# EYEO_Flower3.net
KiCad netlist of a schematic drawn in EAGLE
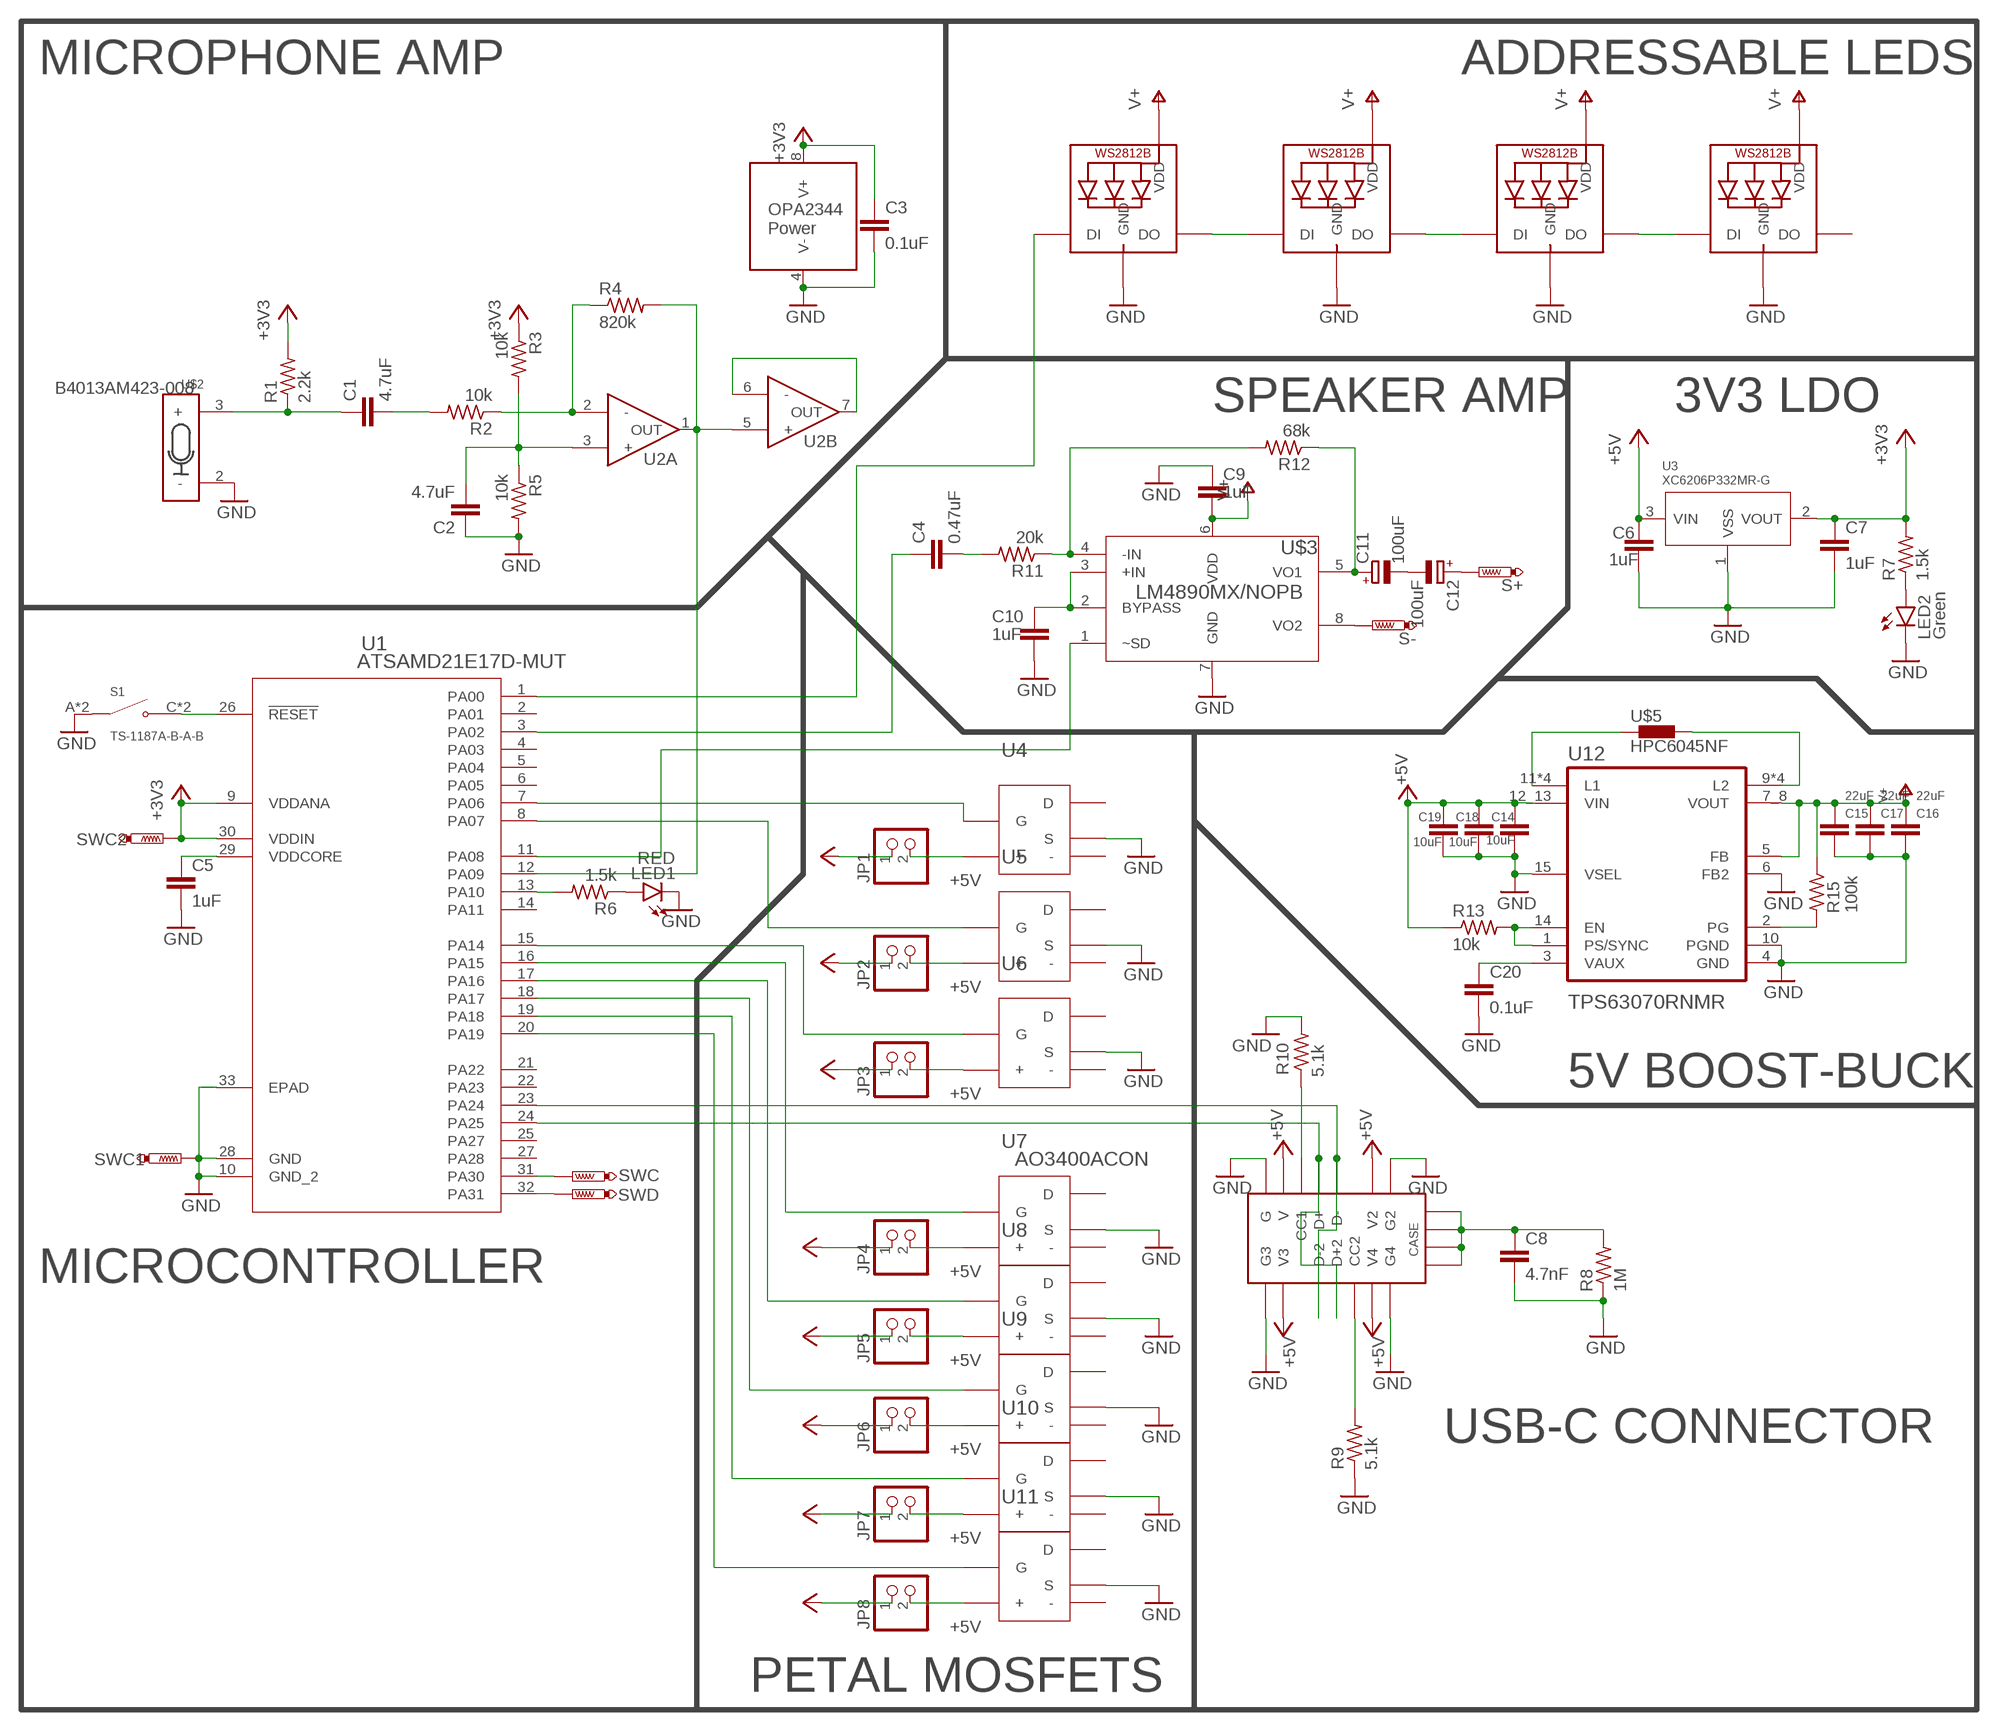
[diagram p0: schematic, sheet 1]

(export (version "E")
  (design (tool "Eeschema 10.0.6"))
  (components
    (comp (ref "C1")
      (value "4.7uF")
      (footprint "eagle-import:C0603")
      (fields (field (name "LCSC_PART") "C19666"))
      (libsource (lib "eagle-import") (part "C-EUC0603"))
    )
    (comp (ref "C2")
      (value "4.7uF")
      (footprint "eagle-import:C0603")
      (fields (field (name "LCSC_PART") "C19666"))
      (libsource (lib "eagle-import") (part "C-EUC0603"))
    )
    (comp (ref "C3")
      (value "0.1uF")
      (footprint "eagle-import:C0402")
      (fields (field (name "LCSC_PART") "C307331"))
      (libsource (lib "eagle-import") (part "C-EUC0402"))
    )
    (comp (ref "C4")
      (value "0.47uF")
      (footprint "eagle-import:C0603")
      (fields (field (name "LCSC_PART") "C1623"))
      (libsource (lib "eagle-import") (part "C-EUC0603"))
    )
    (comp (ref "C5")
      (value "1uF")
      (footprint "eagle-import:C0603")
      (fields (field (name "LCSC_PART") "C15849"))
      (libsource (lib "eagle-import") (part "C-EUC0603"))
    )
    (comp (ref "C6")
      (value "1uF")
      (footprint "eagle-import:C0603")
      (fields (field (name "LCSC_PART") "C15849"))
      (libsource (lib "eagle-import") (part "C-EUC0603"))
    )
    (comp (ref "C7")
      (value "1uF")
      (footprint "eagle-import:C0603")
      (fields (field (name "LCSC_PART") "C15849"))
      (libsource (lib "eagle-import") (part "C-EUC0603"))
    )
    (comp (ref "C8")
      (value "4.7nF")
      (footprint "eagle-import:C0402")
      (fields (field (name "LCSC_PART") "C1538"))
      (libsource (lib "eagle-import") (part "C-EUC0402"))
    )
    (comp (ref "C9")
      (value "1uF")
      (footprint "eagle-import:C0603")
      (fields (field (name "LCSC_PART") "C15849"))
      (libsource (lib "eagle-import") (part "C-EUC0603"))
    )
    (comp (ref "C10")
      (value "1uF")
      (footprint "eagle-import:C0603")
      (fields (field (name "LCSC_PART") "C15849"))
      (libsource (lib "eagle-import") (part "C-EUC0603"))
    )
    (comp (ref "C11")
      (value "100uF")
      (footprint "eagle-import:153CLV-0505")
      (fields (field (name "LCSC_PART") "C3347"))
      (libsource (lib "eagle-import") (part "CPOL-EU153CLV-0505"))
    )
    (comp (ref "C12")
      (value "100uF")
      (footprint "eagle-import:153CLV-0505")
      (fields (field (name "LCSC_PART") "C3347"))
      (libsource (lib "eagle-import") (part "CPOL-EU153CLV-0505"))
    )
    (comp (ref "C14")
      (value "10uF")
      (footprint "eagle-import:C0603")
      (fields (field (name "LCSC_PART") "C96446"))
      (libsource (lib "eagle-import") (part "C-EUC0603"))
    )
    (comp (ref "C15")
      (value "22uF")
      (footprint "eagle-import:C0603")
      (fields (field (name "LCSC_PART") "C59461"))
      (libsource (lib "eagle-import") (part "C-EUC0603"))
    )
    (comp (ref "C16")
      (value "22uF")
      (footprint "eagle-import:C0603")
      (fields (field (name "LCSC_PART") "C59461"))
      (libsource (lib "eagle-import") (part "C-EUC0603"))
    )
    (comp (ref "C17")
      (value "22uF")
      (footprint "eagle-import:C0603")
      (fields (field (name "LCSC_PART") "C59461"))
      (libsource (lib "eagle-import") (part "C-EUC0603"))
    )
    (comp (ref "C18")
      (value "10uF")
      (footprint "eagle-import:C0603")
      (fields (field (name "LCSC_PART") "C96446"))
      (libsource (lib "eagle-import") (part "C-EUC0603"))
    )
    (comp (ref "C19")
      (value "10uF")
      (footprint "eagle-import:C0603")
      (fields (field (name "LCSC_PART") "C96446"))
      (libsource (lib "eagle-import") (part "C-EUC0603"))
    )
    (comp (ref "C20")
      (value "0.1uF")
      (footprint "eagle-import:C0402")
      (fields (field (name "LCSC_PART") "C307331"))
      (libsource (lib "eagle-import") (part "C-EUC0402"))
    )
    (comp (ref "JP1")
      (value "PINHD-1X2")
      (footprint "eagle-import:1X02")
      (fields (field (name "LCSC_PART") "C2889984"))
      (libsource (lib "eagle-import") (part "PINHD-1X2"))
    )
    (comp (ref "JP2")
      (value "PINHD-1X2")
      (footprint "eagle-import:1X02")
      (fields (field (name "LCSC_PART") "C2889984"))
      (libsource (lib "eagle-import") (part "PINHD-1X2"))
    )
    (comp (ref "JP3")
      (value "PINHD-1X2")
      (footprint "eagle-import:1X02")
      (fields (field (name "LCSC_PART") "C2889984"))
      (libsource (lib "eagle-import") (part "PINHD-1X2"))
    )
    (comp (ref "JP4")
      (value "PINHD-1X2")
      (footprint "eagle-import:1X02")
      (fields (field (name "LCSC_PART") "C2889984"))
      (libsource (lib "eagle-import") (part "PINHD-1X2"))
    )
    (comp (ref "JP5")
      (value "PINHD-1X2")
      (footprint "eagle-import:1X02")
      (fields (field (name "LCSC_PART") "C2889984"))
      (libsource (lib "eagle-import") (part "PINHD-1X2"))
    )
    (comp (ref "JP6")
      (value "PINHD-1X2")
      (footprint "eagle-import:1X02")
      (fields (field (name "LCSC_PART") "C2889984"))
      (libsource (lib "eagle-import") (part "PINHD-1X2"))
    )
    (comp (ref "JP7")
      (value "PINHD-1X2")
      (footprint "eagle-import:1X02")
      (fields (field (name "LCSC_PART") "C2889984"))
      (libsource (lib "eagle-import") (part "PINHD-1X2"))
    )
    (comp (ref "JP8")
      (value "PINHD-1X2")
      (footprint "eagle-import:1X02")
      (fields (field (name "LCSC_PART") "C2889984"))
      (libsource (lib "eagle-import") (part "PINHD-1X2"))
    )
    (comp (ref "LED1")
      (value "RED")
      (footprint "eagle-import:CHIPLED_0805")
      (fields (field (name "LCSC_PART") "C84256"))
      (libsource (lib "eagle-import") (part "LEDCHIPLED_0805"))
    )
    (comp (ref "LED2")
      (value "Green")
      (footprint "eagle-import:CHIPLED_0603")
      (fields (field (name "LCSC_PART") "C72043"))
      (libsource (lib "eagle-import") (part "LEDCHIPLED_0603"))
    )
    (comp (ref "LED3")
      (value "WS2812B5050")
      (footprint "eagle-import:WS2812B")
      (fields
        (field (name "LCSC_PART") "C2761795")
        (field (name "MF") "Worldsemi")
        (field (name "MP") "WS2812B")
      )
      (libsource (lib "eagle-import") (part "WS2812B5050"))
    )
    (comp (ref "LED4")
      (value "WS2812B5050")
      (footprint "eagle-import:WS2812B")
      (fields
        (field (name "LCSC_PART") "C2761795")
        (field (name "MF") "Worldsemi")
        (field (name "MP") "WS2812B")
      )
      (libsource (lib "eagle-import") (part "WS2812B5050"))
    )
    (comp (ref "LED5")
      (value "WS2812B5050")
      (footprint "eagle-import:WS2812B")
      (fields
        (field (name "LCSC_PART") "C2761795")
        (field (name "MF") "Worldsemi")
        (field (name "MP") "WS2812B")
      )
      (libsource (lib "eagle-import") (part "WS2812B5050"))
    )
    (comp (ref "LED6")
      (value "WS2812B5050")
      (footprint "eagle-import:WS2812B")
      (fields
        (field (name "LCSC_PART") "C2761795")
        (field (name "MF") "Worldsemi")
        (field (name "MP") "WS2812B")
      )
      (libsource (lib "eagle-import") (part "WS2812B5050"))
    )
    (comp (ref "R1")
      (value "2.2k")
      (footprint "eagle-import:R0402")
      (fields (field (name "LCSC_PART") "C25879"))
      (libsource (lib "eagle-import") (part "R-US_R0402"))
    )
    (comp (ref "R2")
      (value "10k")
      (footprint "eagle-import:R0402")
      (fields (field (name "LCSC_PART") "C25744"))
      (libsource (lib "eagle-import") (part "R-US_R0402"))
    )
    (comp (ref "R3")
      (value "10k")
      (footprint "eagle-import:R0402")
      (fields (field (name "LCSC_PART") "C25744"))
      (libsource (lib "eagle-import") (part "R-US_R0402"))
    )
    (comp (ref "R4")
      (value "820k")
      (footprint "eagle-import:R0402")
      (fields (field (name "LCSC_PART") "C67558"))
      (libsource (lib "eagle-import") (part "R-US_R0402"))
    )
    (comp (ref "R5")
      (value "10k")
      (footprint "eagle-import:R0402")
      (fields (field (name "LCSC_PART") "C25744"))
      (libsource (lib "eagle-import") (part "R-US_R0402"))
    )
    (comp (ref "R6")
      (value "1.5k")
      (footprint "eagle-import:R0402")
      (fields (field (name "LCSC_PART") "C25867"))
      (libsource (lib "eagle-import") (part "R-US_R0402"))
    )
    (comp (ref "R7")
      (value "1.5k")
      (footprint "eagle-import:R0402")
      (fields (field (name "LCSC_PART") "C25867"))
      (libsource (lib "eagle-import") (part "R-US_R0402"))
    )
    (comp (ref "R8")
      (value "1M")
      (footprint "eagle-import:R0402")
      (fields (field (name "LCSC_PART") "C26083"))
      (libsource (lib "eagle-import") (part "R-US_R0402"))
    )
    (comp (ref "R9")
      (value "5.1k")
      (footprint "eagle-import:R0402")
      (fields (field (name "LCSC_PART") "C25905"))
      (libsource (lib "eagle-import") (part "R-US_R0402"))
    )
    (comp (ref "R10")
      (value "5.1k")
      (footprint "eagle-import:R0402")
      (fields (field (name "LCSC_PART") "C25905"))
      (libsource (lib "eagle-import") (part "R-US_R0402"))
    )
    (comp (ref "R11")
      (value "20k")
      (footprint "eagle-import:R0402")
      (fields (field (name "LCSC_PART") "C25765"))
      (libsource (lib "eagle-import") (part "R-US_R0402"))
    )
    (comp (ref "R12")
      (value "68k")
      (footprint "eagle-import:R0402")
      (fields (field (name "LCSC_PART") "C36871"))
      (libsource (lib "eagle-import") (part "R-US_R0402"))
    )
    (comp (ref "R13")
      (value "10k")
      (footprint "eagle-import:R0402")
      (fields (field (name "LCSC_PART") "C25744"))
      (libsource (lib "eagle-import") (part "R-US_R0402"))
    )
    (comp (ref "R15")
      (value "100k")
      (footprint "eagle-import:R0402")
      (fields (field (name "LCSC_PART") "C25741"))
      (libsource (lib "eagle-import") (part "R-US_R0402"))
    )
    (comp (ref "S+")
      (value "PTR11MM")
      (footprint "eagle-import:1MM")
      (fields (field (name "LCSC_PART") "C238122"))
      (libsource (lib "eagle-import") (part "PTR11MM"))
    )
    (comp (ref "S-")
      (value "PTR11MM")
      (footprint "eagle-import:1MM")
      (fields (field (name "LCSC_PART") "C238122"))
      (libsource (lib "eagle-import") (part "PTR11MM"))
    )
    (comp (ref "S1")
      (value "TS-1187A-B-A-B")
      (footprint "eagle-import:SW_TS-1187A-B-A-B")
      (fields (field (name "MF") "XKB Industrial Precision") (field (name "LCSC_PART") "C318884"))
      (libsource (lib "eagle-import") (part "TS-1187A-B-A-B"))
    )
    (comp (ref "SWC")
      (value "PTR1PAD1-13")
      (footprint "eagle-import:P1-13")
      (libsource (lib "eagle-import") (part "PTR1PAD1-13"))
    )
    (comp (ref "SWC1")
      (value "PTR1PAD1-13")
      (footprint "eagle-import:P1-13")
      (libsource (lib "eagle-import") (part "PTR1PAD1-13"))
    )
    (comp (ref "SWC2")
      (value "PTR1PAD1-13")
      (footprint "eagle-import:P1-13")
      (libsource (lib "eagle-import") (part "PTR1PAD1-13"))
    )
    (comp (ref "SWD")
      (value "PTR1PAD1-13")
      (footprint "eagle-import:P1-13")
      (libsource (lib "eagle-import") (part "PTR1PAD1-13"))
    )
    (comp (ref "U$1")
      (value "USB-C")
      (footprint "eagle-import:918-418K2022Y40000")
      (fields (field (name "LCSC_PART") "C168704"))
      (libsource (lib "eagle-import") (part "USB-C"))
    )
    (comp (ref "U$2")
      (value "B4013AM423")
      (footprint "eagle-import:B4013AM423")
      (fields (field (name "LCSC_PART") "C233794") (field (name "NUM") "B4013AM423-008 "))
      (libsource (lib "eagle-import") (part "B4013AM423"))
    )
    (comp (ref "U$3")
      (value "LM4890MX/NOPB")
      (footprint "eagle-import:M08A")
      (fields
        (field (name "LCSC_PART") "C117476")
        (field (name "COPYRIGHT") "Copyright (C) 2022 Ultra Librarian. All rights reserved.")
      )
      (libsource (lib "eagle-import") (part "LM4890MX/NOPB"))
    )
    (comp (ref "U$5")
      (value "HPC6045NF")
      (footprint "eagle-import:HPC6045NF")
      (fields (field (name "LCSC_PART") "C357076"))
      (libsource (lib "eagle-import") (part "HPC6045NF"))
    )
    (comp (ref "U1")
      (value "ATSAMD21E17D-MUT")
      (footprint "eagle-import:QFN32_5X5MC_MCH")
      (fields (field (name "COPYRIGHT") "Copyright (C) 2022 Ultra Librarian. All rights reserved."))
      (libsource (lib "eagle-import") (part "ATSAMD21E17D-MUT"))
    )
    (comp (ref "U2")
      (value "OPA2344UA")
      (footprint "eagle-import:D8")
      (fields
        (field (name "LCSC_PART") "C202213")
        (field (name "COPYRIGHT") "Copyright (C) 2022 Ultra Librarian. All rights reserved.")
      )
      (libsource (lib "eagle-import") (part "OPA2344UA"))
    )
    (comp (ref "U3")
      (value "XC6206P332MR-G")
      (footprint "eagle-import:SOT-23")
      (fields (field (name "MF") "Torex") (field (name "LCSC_PART") "C5446"))
      (libsource (lib "eagle-import") (part "PMIC-LDO-XC6206P332MR-G(SOT23)"))
    )
    (comp (ref "U4")
      (value "AO3400ACON")
      (footprint "eagle-import:SOT23-BCE-CON")
      (fields (field (name "LCSC_PART") "C20917"))
      (libsource (lib "eagle-import") (part "AO3400ACON"))
    )
    (comp (ref "U5")
      (value "AO3400ACON")
      (footprint "eagle-import:SOT23-BCE-CON")
      (fields (field (name "LCSC_PART") "C20917"))
      (libsource (lib "eagle-import") (part "AO3400ACON"))
    )
    (comp (ref "U6")
      (value "AO3400ACON")
      (footprint "eagle-import:SOT23-BCE-CON")
      (fields (field (name "LCSC_PART") "C20917"))
      (libsource (lib "eagle-import") (part "AO3400ACON"))
    )
    (comp (ref "U7")
      (value "AO3400ACON")
      (footprint "eagle-import:SOT23-BCE-CON")
      (fields (field (name "LCSC_PART") "C20917"))
      (libsource (lib "eagle-import") (part "AO3400ACON"))
    )
    (comp (ref "U8")
      (value "AO3400ACON")
      (footprint "eagle-import:SOT23-BCE-CON")
      (fields (field (name "LCSC_PART") "C20917"))
      (libsource (lib "eagle-import") (part "AO3400ACON"))
    )
    (comp (ref "U9")
      (value "AO3400ACON")
      (footprint "eagle-import:SOT23-BCE-CON")
      (fields (field (name "LCSC_PART") "C20917"))
      (libsource (lib "eagle-import") (part "AO3400ACON"))
    )
    (comp (ref "U10")
      (value "AO3400ACON")
      (footprint "eagle-import:SOT23-BCE-CON")
      (fields (field (name "LCSC_PART") "C20917"))
      (libsource (lib "eagle-import") (part "AO3400ACON"))
    )
    (comp (ref "U11")
      (value "AO3400ACON")
      (footprint "eagle-import:SOT23-BCE-CON")
      (fields (field (name "LCSC_PART") "C20917"))
      (libsource (lib "eagle-import") (part "AO3400ACON"))
    )
    (comp (ref "U12")
      (value "TPS63070RNMR")
      (footprint "eagle-import:VREG_TPS63070RNMR")
      (fields (field (name "LCSC_PART") "C2876599") (field (name "MF") "Texas Instruments"))
      (libsource (lib "eagle-import") (part "TPS63070RNMR"))
    )
  )
  (nets
    (net (code "1") (name "+3V3") (class "Default")
      (node (ref "C3") (pin "1") (pinfunction "1_1") (pintype "passive"))
      (node (ref "C7") (pin "1") (pinfunction "1_1") (pintype "passive"))
      (node (ref "R1") (pin "2") (pinfunction "2_2") (pintype "passive"))
      (node (ref "R3") (pin "1") (pinfunction "1_1") (pintype "passive"))
      (node (ref "R7") (pin "2") (pinfunction "2_2") (pintype "passive"))
      (node (ref "SWC2") (pin "TP") (pinfunction "TP_TP") (pintype "input"))
      (node (ref "U1") (pin "30") (pinfunction "VDDIN_30") (pintype "power_in"))
      (node (ref "U1") (pin "9") (pinfunction "VDDANA_9") (pintype "power_in"))
      (node (ref "U2") (pin "8") (pinfunction "V+_8") (pintype "bidirectional"))
      (node (ref "U3") (pin "2") (pinfunction "VOUT_2") (pintype "output"))
    )
    (net (code "2") (name "+5V") (class "Default")
      (node (ref "C14") (pin "1") (pinfunction "1_1") (pintype "passive"))
      (node (ref "C18") (pin "1") (pinfunction "1_1") (pintype "passive"))
      (node (ref "C19") (pin "1") (pinfunction "1_1") (pintype "passive"))
      (node (ref "C6") (pin "1") (pinfunction "1_1") (pintype "passive"))
      (node (ref "JP1") (pin "1") (pinfunction "1_1") (pintype "passive"))
      (node (ref "JP2") (pin "1") (pinfunction "1_1") (pintype "passive"))
      (node (ref "JP3") (pin "1") (pinfunction "1_1") (pintype "passive"))
      (node (ref "JP4") (pin "1") (pinfunction "1_1") (pintype "passive"))
      (node (ref "JP5") (pin "1") (pinfunction "1_1") (pintype "passive"))
      (node (ref "JP6") (pin "1") (pinfunction "1_1") (pintype "passive"))
      (node (ref "JP7") (pin "1") (pinfunction "1_1") (pintype "passive"))
      (node (ref "JP8") (pin "1") (pinfunction "1_1") (pintype "passive"))
      (node (ref "R13") (pin "1") (pinfunction "1_1") (pintype "passive"))
      (node (ref "U$1") (pin "V") (pinfunction "V_V") (pintype "bidirectional"))
      (node (ref "U$1") (pin "V2") (pinfunction "V2_V2") (pintype "bidirectional"))
      (node (ref "U$1") (pin "V3") (pinfunction "V3_V3") (pintype "bidirectional"))
      (node (ref "U$1") (pin "V4") (pinfunction "V4_V4") (pintype "bidirectional"))
      (node (ref "U12") (pin "12_13") (pinfunction "VIN_12_13") (pintype "input"))
      (node (ref "U3") (pin "3") (pinfunction "VIN_3") (pintype "input"))
    )
    (net (code "3") (name "GND") (class "Default")
      (node (ref "C10") (pin "2") (pinfunction "2_2") (pintype "passive"))
      (node (ref "C14") (pin "2") (pinfunction "2_2") (pintype "passive"))
      (node (ref "C15") (pin "2") (pinfunction "2_2") (pintype "passive"))
      (node (ref "C16") (pin "2") (pinfunction "2_2") (pintype "passive"))
      (node (ref "C17") (pin "2") (pinfunction "2_2") (pintype "passive"))
      (node (ref "C18") (pin "2") (pinfunction "2_2") (pintype "passive"))
      (node (ref "C19") (pin "2") (pinfunction "2_2") (pintype "passive"))
      (node (ref "C2") (pin "1") (pinfunction "1_1") (pintype "passive"))
      (node (ref "C20") (pin "2") (pinfunction "2_2") (pintype "passive"))
      (node (ref "C3") (pin "2") (pinfunction "2_2") (pintype "passive"))
      (node (ref "C5") (pin "2") (pinfunction "2_2") (pintype "passive"))
      (node (ref "C6") (pin "2") (pinfunction "2_2") (pintype "passive"))
      (node (ref "C7") (pin "2") (pinfunction "2_2") (pintype "passive"))
      (node (ref "C8") (pin "2") (pinfunction "2_2") (pintype "passive"))
      (node (ref "C9") (pin "1") (pinfunction "1_1") (pintype "passive"))
      (node (ref "LED1") (pin "C") (pinfunction "C_C") (pintype "passive"))
      (node (ref "LED2") (pin "C") (pinfunction "C_C") (pintype "passive"))
      (node (ref "LED3") (pin "3-GND") (pinfunction "GND_3-GND") (pintype "power_in"))
      (node (ref "LED4") (pin "3-GND") (pinfunction "GND_3-GND") (pintype "power_in"))
      (node (ref "LED5") (pin "3-GND") (pinfunction "GND_3-GND") (pintype "power_in"))
      (node (ref "LED6") (pin "3-GND") (pinfunction "GND_3-GND") (pintype "power_in"))
      (node (ref "R10") (pin "2") (pinfunction "2_2") (pintype "passive"))
      (node (ref "R5") (pin "2") (pinfunction "2_2") (pintype "passive"))
      (node (ref "R8") (pin "1") (pinfunction "1_1") (pintype "passive"))
      (node (ref "R9") (pin "1") (pinfunction "1_1") (pintype "passive"))
      (node (ref "S1") (pin "A") (pinfunction "COM_A") (pintype "passive"))
      (node (ref "S1") (pin "B") (pinfunction "COM_B") (pintype "passive"))
      (node (ref "SWC1") (pin "TP") (pinfunction "TP_TP") (pintype "input"))
      (node (ref "U$1") (pin "G") (pinfunction "G_G") (pintype "bidirectional"))
      (node (ref "U$1") (pin "G2") (pinfunction "G2_G2") (pintype "bidirectional"))
      (node (ref "U$1") (pin "G3") (pinfunction "G3_G3") (pintype "bidirectional"))
      (node (ref "U$1") (pin "G4") (pinfunction "G4_G4") (pintype "bidirectional"))
      (node (ref "U$2") (pin "2") (pinfunction "-_2") (pintype "bidirectional"))
      (node (ref "U$3") (pin "7") (pinfunction "GND_7") (pintype "power_in"))
      (node (ref "U1") (pin "10") (pinfunction "GND_2_10") (pintype "passive"))
      (node (ref "U1") (pin "28") (pinfunction "GND_28") (pintype "passive"))
      (node (ref "U1") (pin "33") (pinfunction "EPAD_33") (pintype "passive"))
      (node (ref "U10") (pin "S") (pinfunction "S_S") (pintype "passive"))
      (node (ref "U11") (pin "S") (pinfunction "S_S") (pintype "passive"))
      (node (ref "U12") (pin "10") (pinfunction "PGND_10") (pintype "power_in"))
      (node (ref "U12") (pin "15") (pinfunction "VSEL_15") (pintype "input"))
      (node (ref "U12") (pin "4") (pinfunction "GND_4") (pintype "power_in"))
      (node (ref "U12") (pin "6") (pinfunction "FB2_6") (pintype "output"))
      (node (ref "U2") (pin "4") (pinfunction "V-_4") (pintype "bidirectional"))
      (node (ref "U3") (pin "1") (pinfunction "VSS_1") (pintype "power_in"))
      (node (ref "U4") (pin "S") (pinfunction "S_S") (pintype "passive"))
      (node (ref "U5") (pin "S") (pinfunction "S_S") (pintype "passive"))
      (node (ref "U6") (pin "S") (pinfunction "S_S") (pintype "passive"))
      (node (ref "U7") (pin "S") (pinfunction "S_S") (pintype "passive"))
      (node (ref "U8") (pin "S") (pinfunction "S_S") (pintype "passive"))
      (node (ref "U9") (pin "S") (pinfunction "S_S") (pintype "passive"))
    )
    (net (code "4") (name "Net-(C1-Pad2)") (class "Default")
      (node (ref "C1") (pin "2") (pinfunction "2_2") (pintype "passive"))
      (node (ref "R2") (pin "2") (pinfunction "2_2") (pintype "passive"))
    )
    (net (code "5") (name "Net-(C4-Pad2)") (class "Default")
      (node (ref "C4") (pin "2") (pinfunction "2_2") (pintype "passive"))
      (node (ref "R11") (pin "2") (pinfunction "2_2") (pintype "passive"))
    )
    (net (code "6") (name "Net-(C11-Pad-)") (class "Default")
      (node (ref "C11") (pin "-") (pinfunction "-_-") (pintype "passive"))
      (node (ref "C12") (pin "-") (pinfunction "-_-") (pintype "passive"))
    )
    (net (code "7") (name "Net-(C12-Pad+)") (class "Default")
      (node (ref "C12") (pin "+") (pinfunction "+_+") (pintype "passive"))
      (node (ref "S+") (pin "TP") (pinfunction "TP_TP") (pintype "input"))
    )
    (net (code "8") (name "Net-(JP1-Pad2)") (class "Default")
      (node (ref "JP1") (pin "2") (pinfunction "2_2") (pintype "passive"))
      (node (ref "U4") (pin "+") (pinfunction "+_+") (pintype "bidirectional"))
    )
    (net (code "9") (name "Net-(JP2-Pad2)") (class "Default")
      (node (ref "JP2") (pin "2") (pinfunction "2_2") (pintype "passive"))
      (node (ref "U5") (pin "+") (pinfunction "+_+") (pintype "bidirectional"))
    )
    (net (code "10") (name "Net-(JP3-Pad2)") (class "Default")
      (node (ref "JP3") (pin "2") (pinfunction "2_2") (pintype "passive"))
      (node (ref "U6") (pin "+") (pinfunction "+_+") (pintype "bidirectional"))
    )
    (net (code "11") (name "Net-(JP4-Pad2)") (class "Default")
      (node (ref "JP4") (pin "2") (pinfunction "2_2") (pintype "passive"))
      (node (ref "U7") (pin "+") (pinfunction "+_+") (pintype "bidirectional"))
    )
    (net (code "12") (name "Net-(JP5-Pad2)") (class "Default")
      (node (ref "JP5") (pin "2") (pinfunction "2_2") (pintype "passive"))
      (node (ref "U8") (pin "+") (pinfunction "+_+") (pintype "bidirectional"))
    )
    (net (code "13") (name "Net-(JP6-Pad2)") (class "Default")
      (node (ref "JP6") (pin "2") (pinfunction "2_2") (pintype "passive"))
      (node (ref "U9") (pin "+") (pinfunction "+_+") (pintype "bidirectional"))
    )
    (net (code "14") (name "Net-(JP7-Pad2)") (class "Default")
      (node (ref "JP7") (pin "2") (pinfunction "2_2") (pintype "passive"))
      (node (ref "U10") (pin "+") (pinfunction "+_+") (pintype "bidirectional"))
    )
    (net (code "15") (name "Net-(JP8-Pad2)") (class "Default")
      (node (ref "JP8") (pin "2") (pinfunction "2_2") (pintype "passive"))
      (node (ref "U11") (pin "+") (pinfunction "+_+") (pintype "bidirectional"))
    )
    (net (code "16") (name "Net-(LED1-PadA)") (class "Default")
      (node (ref "LED1") (pin "A") (pinfunction "A_A") (pintype "passive"))
      (node (ref "R6") (pin "1") (pinfunction "1_1") (pintype "passive"))
    )
    (net (code "17") (name "Net-(LED2-PadA)") (class "Default")
      (node (ref "LED2") (pin "A") (pinfunction "A_A") (pintype "passive"))
      (node (ref "R7") (pin "1") (pinfunction "1_1") (pintype "passive"))
    )
    (net (code "18") (name "Net-(LED3-DI)") (class "Default")
      (node (ref "LED3") (pin "4-DIN") (pinfunction "DI_4-DIN") (pintype "input"))
      (node (ref "U1") (pin "1") (pinfunction "PA00_1") (pintype "bidirectional"))
    )
    (net (code "19") (name "Net-(LED3-DO)") (class "Default")
      (node (ref "LED3") (pin "2-DOUT") (pinfunction "DO_2-DOUT") (pintype "output"))
      (node (ref "LED4") (pin "4-DIN") (pinfunction "DI_4-DIN") (pintype "input"))
    )
    (net (code "20") (name "Net-(LED4-DO)") (class "Default")
      (node (ref "LED4") (pin "2-DOUT") (pinfunction "DO_2-DOUT") (pintype "output"))
      (node (ref "LED5") (pin "4-DIN") (pinfunction "DI_4-DIN") (pintype "input"))
    )
    (net (code "21") (name "Net-(LED5-DO)") (class "Default")
      (node (ref "LED5") (pin "2-DOUT") (pinfunction "DO_2-DOUT") (pintype "output"))
      (node (ref "LED6") (pin "4-DIN") (pinfunction "DI_4-DIN") (pintype "input"))
    )
    (net (code "22") (name "Net-(R9-Pad2)") (class "Default")
      (node (ref "R9") (pin "2") (pinfunction "2_2") (pintype "passive"))
      (node (ref "U$1") (pin "CC2") (pinfunction "CC2_CC2") (pintype "bidirectional"))
    )
    (net (code "23") (name "Net-(R10-Pad1)") (class "Default")
      (node (ref "R10") (pin "1") (pinfunction "1_1") (pintype "passive"))
      (node (ref "U$1") (pin "CC1") (pinfunction "CC1_CC1") (pintype "bidirectional"))
    )
    (net (code "24") (name "Net-(U$1-1)") (class "Default")
      (node (ref "C8") (pin "1") (pinfunction "1_1") (pintype "passive"))
      (node (ref "R8") (pin "2") (pinfunction "2_2") (pintype "passive"))
      (node (ref "U$1") (pin "OG1") (pinfunction "1_OG1") (pintype "bidirectional"))
      (node (ref "U$1") (pin "OG2") (pinfunction "2_OG2") (pintype "bidirectional"))
      (node (ref "U$1") (pin "OG3") (pinfunction "3_OG3") (pintype "bidirectional"))
      (node (ref "U$1") (pin "OG4") (pinfunction "4_OG4") (pintype "bidirectional"))
    )
    (net (code "25") (name "Net-(U$2-+)") (class "Default")
      (node (ref "C1") (pin "1") (pinfunction "1_1") (pintype "passive"))
      (node (ref "R1") (pin "1") (pinfunction "1_1") (pintype "passive"))
      (node (ref "U$2") (pin "3") (pinfunction "+_3") (pintype "bidirectional"))
    )
    (net (code "26") (name "Net-(U$3-+IN)") (class "Default")
      (node (ref "C10") (pin "1") (pinfunction "1_1") (pintype "passive"))
      (node (ref "U$3") (pin "2") (pinfunction "BYPASS_2") (pintype "passive"))
      (node (ref "U$3") (pin "3") (pinfunction "+IN_3") (pintype "input"))
    )
    (net (code "27") (name "Net-(U$3--IN)") (class "Default")
      (node (ref "R11") (pin "1") (pinfunction "1_1") (pintype "passive"))
      (node (ref "R12") (pin "2") (pinfunction "2_2") (pintype "passive"))
      (node (ref "U$3") (pin "4") (pinfunction "-IN_4") (pintype "input"))
    )
    (net (code "28") (name "Net-(U$3-VO1)") (class "Default")
      (node (ref "C11") (pin "+") (pinfunction "+_+") (pintype "passive"))
      (node (ref "R12") (pin "1") (pinfunction "1_1") (pintype "passive"))
      (node (ref "U$3") (pin "5") (pinfunction "VO1_5") (pintype "output"))
    )
    (net (code "29") (name "Net-(U$3-VO2)") (class "Default")
      (node (ref "S-") (pin "TP") (pinfunction "TP_TP") (pintype "input"))
      (node (ref "U$3") (pin "8") (pinfunction "VO2_8") (pintype "output"))
    )
    (net (code "30") (name "Net-(U$3-~{SD})") (class "Default")
      (node (ref "U$3") (pin "1") (pinfunction "~{SD}_1") (pintype "input"))
      (node (ref "U1") (pin "11") (pinfunction "PA08_11") (pintype "bidirectional"))
    )
    (net (code "31") (name "Net-(U$5-1)") (class "Default")
      (node (ref "U$5") (pin "P$1") (pinfunction "1_P$1") (pintype "passive"))
      (node (ref "U12") (pin "11") (pinfunction "L1_11") (pintype "bidirectional"))
      (node (ref "U12") (pin "11_1") (pinfunction "L1_11_1") (pintype "bidirectional"))
      (node (ref "U12") (pin "11_2") (pinfunction "L1_11_2") (pintype "bidirectional"))
      (node (ref "U12") (pin "11_3") (pinfunction "L1_11_3") (pintype "bidirectional"))
    )
    (net (code "32") (name "Net-(U$5-2)") (class "Default")
      (node (ref "U$5") (pin "P$2") (pinfunction "2_P$2") (pintype "passive"))
      (node (ref "U12") (pin "9") (pinfunction "L2_9") (pintype "bidirectional"))
      (node (ref "U12") (pin "9_1") (pinfunction "L2_9_1") (pintype "bidirectional"))
      (node (ref "U12") (pin "9_2") (pinfunction "L2_9_2") (pintype "bidirectional"))
      (node (ref "U12") (pin "9_3") (pinfunction "L2_9_3") (pintype "bidirectional"))
    )
    (net (code "33") (name "Net-(U1-PA02)") (class "Default")
      (node (ref "C4") (pin "1") (pinfunction "1_1") (pintype "passive"))
      (node (ref "U1") (pin "3") (pinfunction "PA02_3") (pintype "bidirectional"))
    )
    (net (code "34") (name "Net-(U1-PA06)") (class "Default")
      (node (ref "U1") (pin "7") (pinfunction "PA06_7") (pintype "bidirectional"))
      (node (ref "U4") (pin "G") (pinfunction "G_G") (pintype "passive"))
    )
    (net (code "35") (name "Net-(U1-PA07)") (class "Default")
      (node (ref "U1") (pin "8") (pinfunction "PA07_8") (pintype "bidirectional"))
      (node (ref "U5") (pin "G") (pinfunction "G_G") (pintype "passive"))
    )
    (net (code "36") (name "Net-(U1-PA09)") (class "Default")
      (node (ref "R4") (pin "2") (pinfunction "2_2") (pintype "passive"))
      (node (ref "U1") (pin "12") (pinfunction "PA09_12") (pintype "bidirectional"))
      (node (ref "U2") (pin "1") (pinfunction "OUT_1") (pintype "bidirectional"))
      (node (ref "U2") (pin "5") (pinfunction "+_5") (pintype "bidirectional"))
    )
    (net (code "37") (name "Net-(U1-PA10)") (class "Default")
      (node (ref "R6") (pin "2") (pinfunction "2_2") (pintype "passive"))
      (node (ref "U1") (pin "13") (pinfunction "PA10_13") (pintype "bidirectional"))
    )
    (net (code "38") (name "Net-(U1-PA14)") (class "Default")
      (node (ref "U1") (pin "15") (pinfunction "PA14_15") (pintype "bidirectional"))
      (node (ref "U6") (pin "G") (pinfunction "G_G") (pintype "passive"))
    )
    (net (code "39") (name "Net-(U1-PA15)") (class "Default")
      (node (ref "U1") (pin "16") (pinfunction "PA15_16") (pintype "bidirectional"))
      (node (ref "U7") (pin "G") (pinfunction "G_G") (pintype "passive"))
    )
    (net (code "40") (name "Net-(U1-PA16)") (class "Default")
      (node (ref "U1") (pin "17") (pinfunction "PA16_17") (pintype "bidirectional"))
      (node (ref "U8") (pin "G") (pinfunction "G_G") (pintype "passive"))
    )
    (net (code "41") (name "Net-(U1-PA17)") (class "Default")
      (node (ref "U1") (pin "18") (pinfunction "PA17_18") (pintype "bidirectional"))
      (node (ref "U9") (pin "G") (pinfunction "G_G") (pintype "passive"))
    )
    (net (code "42") (name "Net-(U1-PA18)") (class "Default")
      (node (ref "U1") (pin "19") (pinfunction "PA18_19") (pintype "bidirectional"))
      (node (ref "U10") (pin "G") (pinfunction "G_G") (pintype "passive"))
    )
    (net (code "43") (name "Net-(U1-PA19)") (class "Default")
      (node (ref "U1") (pin "20") (pinfunction "PA19_20") (pintype "bidirectional"))
      (node (ref "U11") (pin "G") (pinfunction "G_G") (pintype "passive"))
    )
    (net (code "44") (name "Net-(U1-PA24)") (class "Default")
      (node (ref "U$1") (pin "D-") (pinfunction "D-_D-") (pintype "bidirectional"))
      (node (ref "U$1") (pin "D-2") (pinfunction "D-2_D-2") (pintype "bidirectional"))
      (node (ref "U1") (pin "23") (pinfunction "PA24_23") (pintype "bidirectional"))
    )
    (net (code "45") (name "Net-(U1-PA25)") (class "Default")
      (node (ref "U$1") (pin "D+") (pinfunction "D+_D+") (pintype "bidirectional"))
      (node (ref "U$1") (pin "D+2") (pinfunction "D+2_D+2") (pintype "bidirectional"))
      (node (ref "U1") (pin "24") (pinfunction "PA25_24") (pintype "bidirectional"))
    )
    (net (code "46") (name "Net-(U1-PA30)") (class "Default")
      (node (ref "SWC") (pin "TP") (pinfunction "TP_TP") (pintype "input"))
      (node (ref "U1") (pin "31") (pinfunction "PA30_31") (pintype "bidirectional"))
    )
    (net (code "47") (name "Net-(U1-PA31)") (class "Default")
      (node (ref "SWD") (pin "TP") (pinfunction "TP_TP") (pintype "input"))
      (node (ref "U1") (pin "32") (pinfunction "PA31_32") (pintype "bidirectional"))
    )
    (net (code "48") (name "Net-(U1-VDDCORE)") (class "Default")
      (node (ref "C5") (pin "1") (pinfunction "1_1") (pintype "passive"))
      (node (ref "U1") (pin "29") (pinfunction "VDDCORE_29") (pintype "power_in"))
    )
    (net (code "49") (name "Net-(U1-~{RESET})") (class "Default")
      (node (ref "S1") (pin "C") (pinfunction "NO_C") (pintype "passive"))
      (node (ref "S1") (pin "D") (pinfunction "NO_D") (pintype "passive"))
      (node (ref "U1") (pin "26") (pinfunction "~{RESET}_26") (pintype "passive"))
    )
    (net (code "50") (name "Net-(U2A-+)") (class "Default")
      (node (ref "C2") (pin "2") (pinfunction "2_2") (pintype "passive"))
      (node (ref "R3") (pin "2") (pinfunction "2_2") (pintype "passive"))
      (node (ref "R5") (pin "1") (pinfunction "1_1") (pintype "passive"))
      (node (ref "U2") (pin "3") (pinfunction "+_3") (pintype "bidirectional"))
    )
    (net (code "51") (name "Net-(U2A--)") (class "Default")
      (node (ref "R2") (pin "1") (pinfunction "1_1") (pintype "passive"))
      (node (ref "R4") (pin "1") (pinfunction "1_1") (pintype "passive"))
      (node (ref "U2") (pin "2") (pinfunction "-_2") (pintype "bidirectional"))
    )
    (net (code "52") (name "Net-(U2B--)") (class "Default")
      (node (ref "U2") (pin "6") (pinfunction "-_6") (pintype "bidirectional"))
      (node (ref "U2") (pin "7") (pinfunction "OUT_7") (pintype "bidirectional"))
    )
    (net (code "53") (name "Net-(U12-EN)") (class "Default")
      (node (ref "R13") (pin "2") (pinfunction "2_2") (pintype "passive"))
      (node (ref "U12") (pin "1") (pinfunction "PS/SYNC_1") (pintype "input"))
      (node (ref "U12") (pin "14") (pinfunction "EN_14") (pintype "input"))
    )
    (net (code "54") (name "Net-(U12-PG)") (class "Default")
      (node (ref "R15") (pin "2") (pinfunction "2_2") (pintype "passive"))
      (node (ref "U12") (pin "2") (pinfunction "PG_2") (pintype "output"))
    )
    (net (code "55") (name "Net-(U12-VAUX)") (class "Default")
      (node (ref "C20") (pin "1") (pinfunction "1_1") (pintype "passive"))
      (node (ref "U12") (pin "3") (pinfunction "VAUX_3") (pintype "output"))
    )
    (net (code "56") (name "V+") (class "Default")
      (node (ref "C15") (pin "1") (pinfunction "1_1") (pintype "passive"))
      (node (ref "C16") (pin "1") (pinfunction "1_1") (pintype "passive"))
      (node (ref "C17") (pin "1") (pinfunction "1_1") (pintype "passive"))
      (node (ref "C9") (pin "2") (pinfunction "2_2") (pintype "passive"))
      (node (ref "LED3") (pin "1-VDD") (pinfunction "VDD_1-VDD") (pintype "power_in"))
      (node (ref "LED4") (pin "1-VDD") (pinfunction "VDD_1-VDD") (pintype "power_in"))
      (node (ref "LED5") (pin "1-VDD") (pinfunction "VDD_1-VDD") (pintype "power_in"))
      (node (ref "LED6") (pin "1-VDD") (pinfunction "VDD_1-VDD") (pintype "power_in"))
      (node (ref "R15") (pin "1") (pinfunction "1_1") (pintype "passive"))
      (node (ref "U$3") (pin "6") (pinfunction "VDD_6") (pintype "power_in"))
      (node (ref "U12") (pin "5") (pinfunction "FB_5") (pintype "input"))
      (node (ref "U12") (pin "7_8") (pinfunction "VOUT_7_8") (pintype "output"))
    )
    (net (code "57") (name "unconnected-(LED6-DO-Pad2-DOUT)") (class "Default")
      (node (ref "LED6") (pin "2-DOUT") (pinfunction "DO_2-DOUT") (pintype "output"))
    )
    (net (code "58") (name "unconnected-(U1-PA01-Pad2)") (class "Default")
      (node (ref "U1") (pin "2") (pinfunction "PA01_2") (pintype "bidirectional"))
    )
    (net (code "59") (name "unconnected-(U1-PA03-Pad4)") (class "Default")
      (node (ref "U1") (pin "4") (pinfunction "PA03_4") (pintype "bidirectional"))
    )
    (net (code "60") (name "unconnected-(U1-PA04-Pad5)") (class "Default")
      (node (ref "U1") (pin "5") (pinfunction "PA04_5") (pintype "bidirectional"))
    )
    (net (code "61") (name "unconnected-(U1-PA05-Pad6)") (class "Default")
      (node (ref "U1") (pin "6") (pinfunction "PA05_6") (pintype "bidirectional"))
    )
    (net (code "62") (name "unconnected-(U1-PA11-Pad14)") (class "Default")
      (node (ref "U1") (pin "14") (pinfunction "PA11_14") (pintype "bidirectional"))
    )
    (net (code "63") (name "unconnected-(U1-PA22-Pad21)") (class "Default")
      (node (ref "U1") (pin "21") (pinfunction "PA22_21") (pintype "bidirectional"))
    )
    (net (code "64") (name "unconnected-(U1-PA23-Pad22)") (class "Default")
      (node (ref "U1") (pin "22") (pinfunction "PA23_22") (pintype "bidirectional"))
    )
    (net (code "65") (name "unconnected-(U1-PA27-Pad25)") (class "Default")
      (node (ref "U1") (pin "25") (pinfunction "PA27_25") (pintype "bidirectional"))
    )
    (net (code "66") (name "unconnected-(U1-PA28-Pad27)") (class "Default")
      (node (ref "U1") (pin "27") (pinfunction "PA28_27") (pintype "bidirectional"))
    )
    (net (code "67") (name "unconnected-(U4-Pad-)") (class "Default")
      (node (ref "U4") (pin "-") (pinfunction "-_-") (pintype "no_connect"))
    )
    (net (code "68") (name "unconnected-(U4-PadD)") (class "Default")
      (node (ref "U4") (pin "D") (pinfunction "D_D") (pintype "no_connect"))
    )
    (net (code "69") (name "unconnected-(U5-Pad-)") (class "Default")
      (node (ref "U5") (pin "-") (pinfunction "-_-") (pintype "no_connect"))
    )
    (net (code "70") (name "unconnected-(U5-PadD)") (class "Default")
      (node (ref "U5") (pin "D") (pinfunction "D_D") (pintype "no_connect"))
    )
    (net (code "71") (name "unconnected-(U6-Pad-)") (class "Default")
      (node (ref "U6") (pin "-") (pinfunction "-_-") (pintype "no_connect"))
    )
    (net (code "72") (name "unconnected-(U6-PadD)") (class "Default")
      (node (ref "U6") (pin "D") (pinfunction "D_D") (pintype "no_connect"))
    )
    (net (code "73") (name "unconnected-(U7-Pad-)") (class "Default")
      (node (ref "U7") (pin "-") (pinfunction "-_-") (pintype "no_connect"))
    )
    (net (code "74") (name "unconnected-(U7-PadD)") (class "Default")
      (node (ref "U7") (pin "D") (pinfunction "D_D") (pintype "no_connect"))
    )
    (net (code "75") (name "unconnected-(U8-Pad-)") (class "Default")
      (node (ref "U8") (pin "-") (pinfunction "-_-") (pintype "no_connect"))
    )
    (net (code "76") (name "unconnected-(U8-PadD)") (class "Default")
      (node (ref "U8") (pin "D") (pinfunction "D_D") (pintype "no_connect"))
    )
    (net (code "77") (name "unconnected-(U9-Pad-)") (class "Default")
      (node (ref "U9") (pin "-") (pinfunction "-_-") (pintype "no_connect"))
    )
    (net (code "78") (name "unconnected-(U9-PadD)") (class "Default")
      (node (ref "U9") (pin "D") (pinfunction "D_D") (pintype "no_connect"))
    )
    (net (code "79") (name "unconnected-(U10-Pad-)") (class "Default")
      (node (ref "U10") (pin "-") (pinfunction "-_-") (pintype "no_connect"))
    )
    (net (code "80") (name "unconnected-(U10-PadD)") (class "Default")
      (node (ref "U10") (pin "D") (pinfunction "D_D") (pintype "no_connect"))
    )
    (net (code "81") (name "unconnected-(U11-Pad-)") (class "Default")
      (node (ref "U11") (pin "-") (pinfunction "-_-") (pintype "no_connect"))
    )
    (net (code "82") (name "unconnected-(U11-PadD)") (class "Default")
      (node (ref "U11") (pin "D") (pinfunction "D_D") (pintype "no_connect"))
    )
  )
)
